# fitnessband.net
KiCad netlist of a schematic drawn in EAGLE
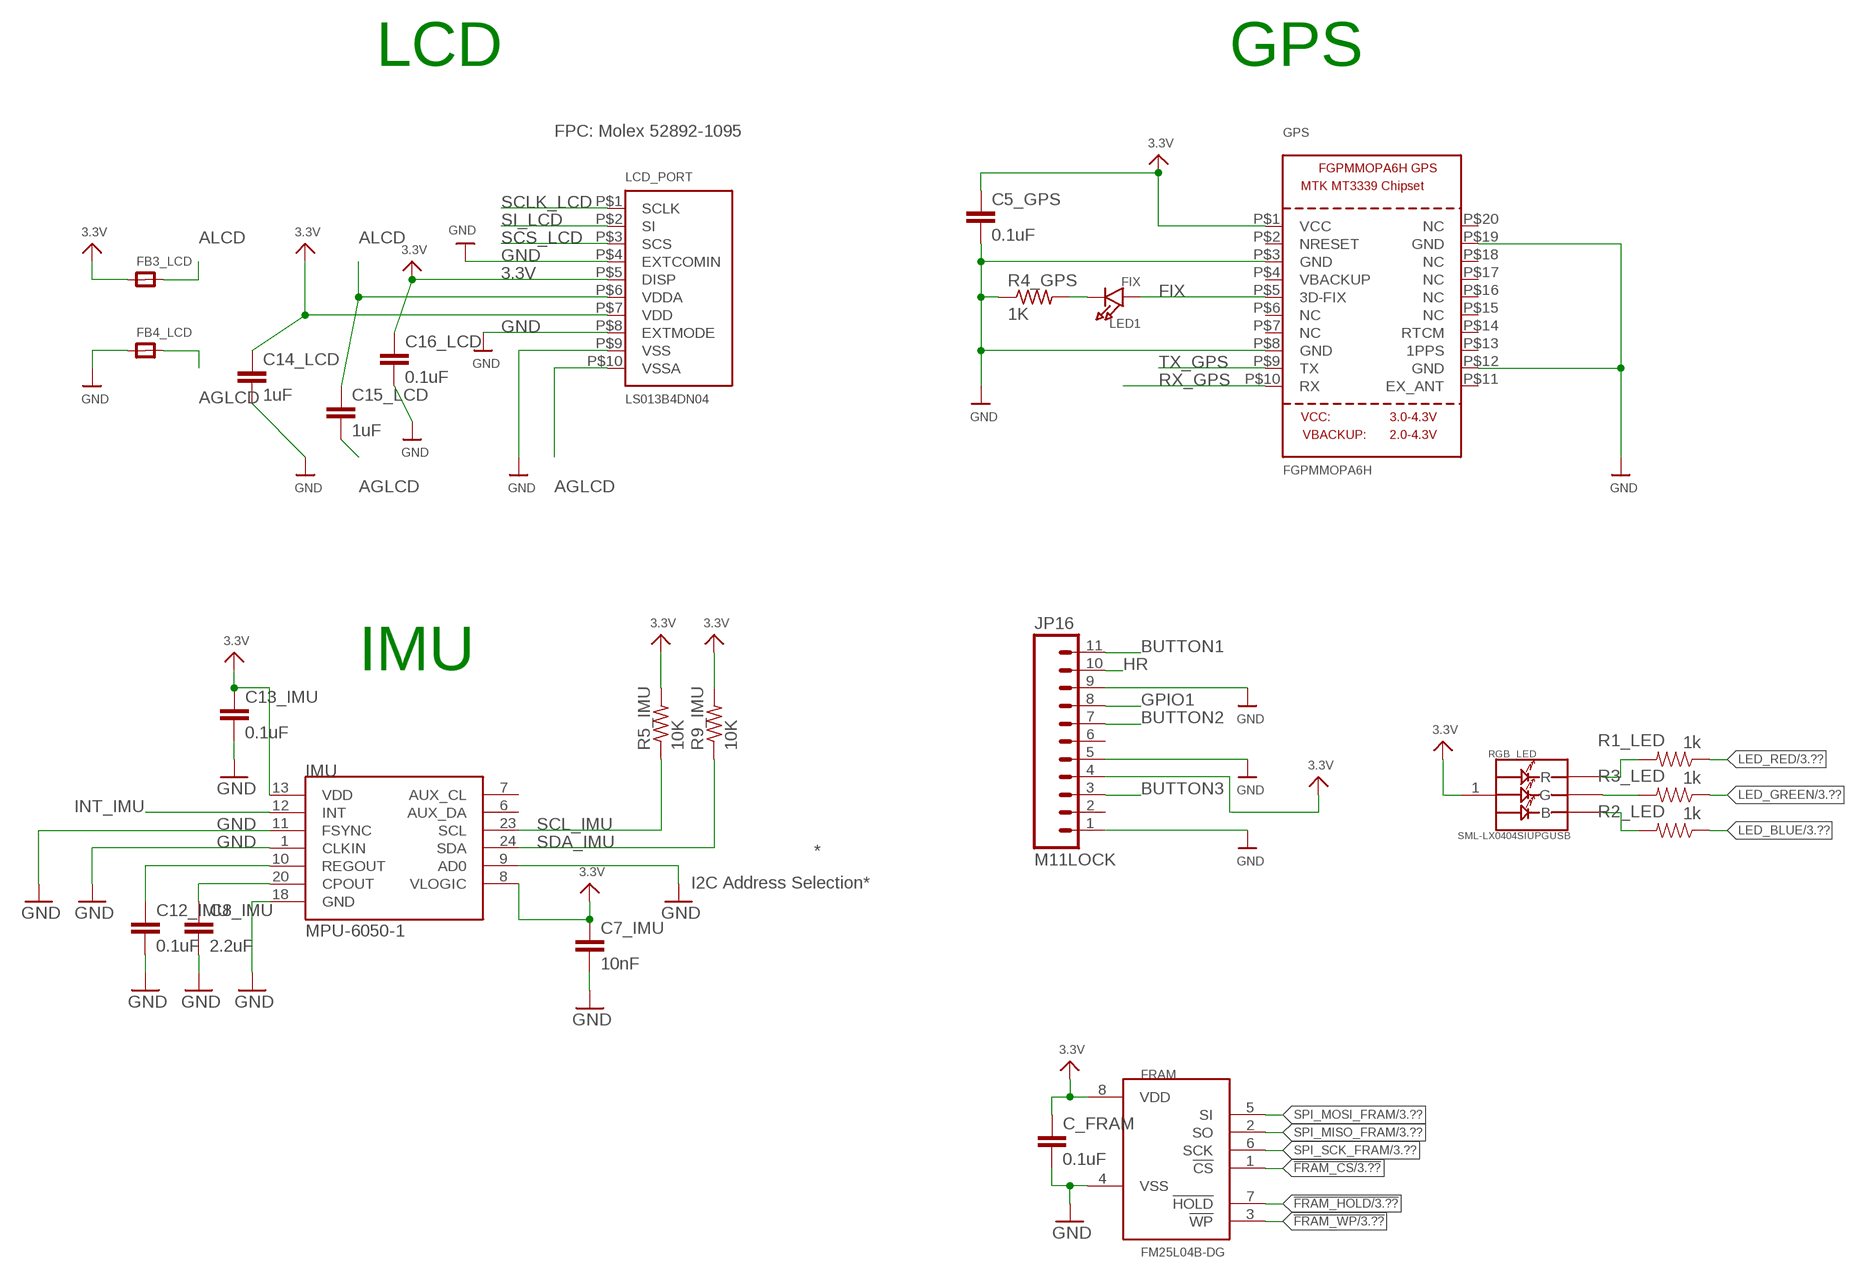
[diagram p0: schematic, sheet 1]
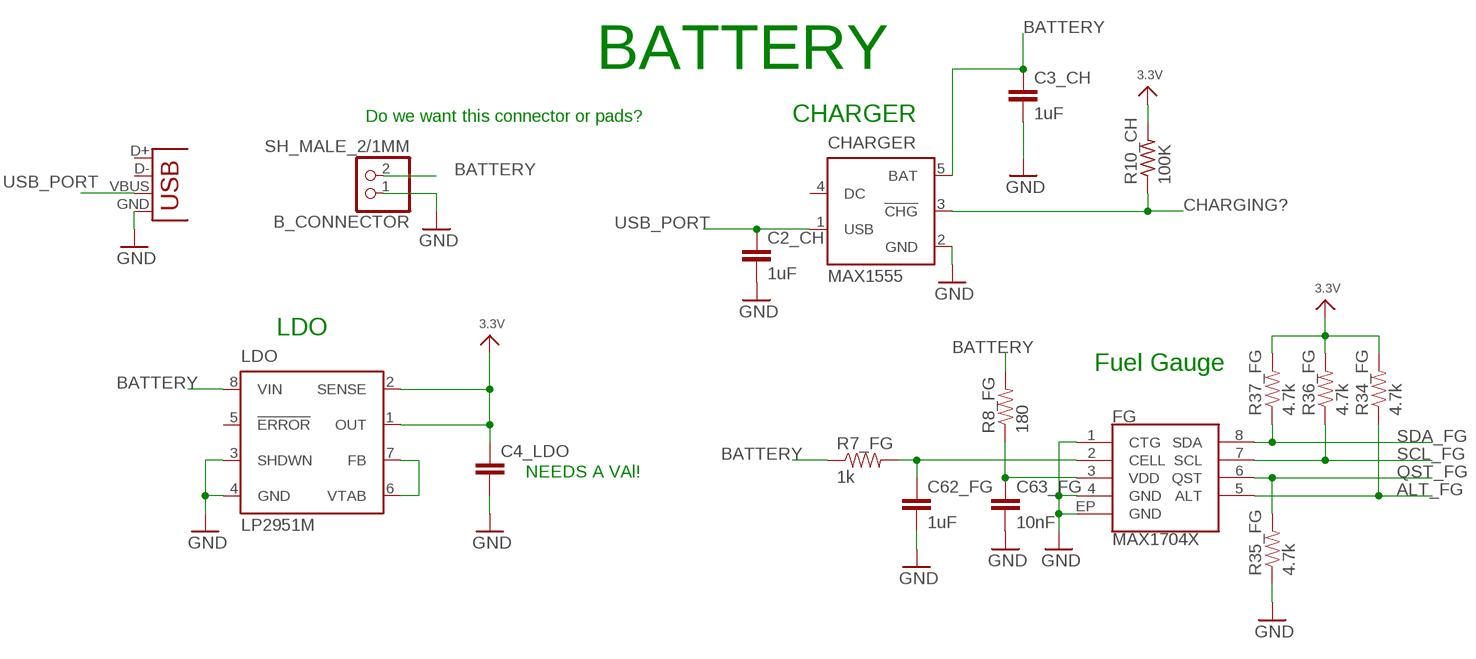
[diagram p1: schematic, sheet 2]
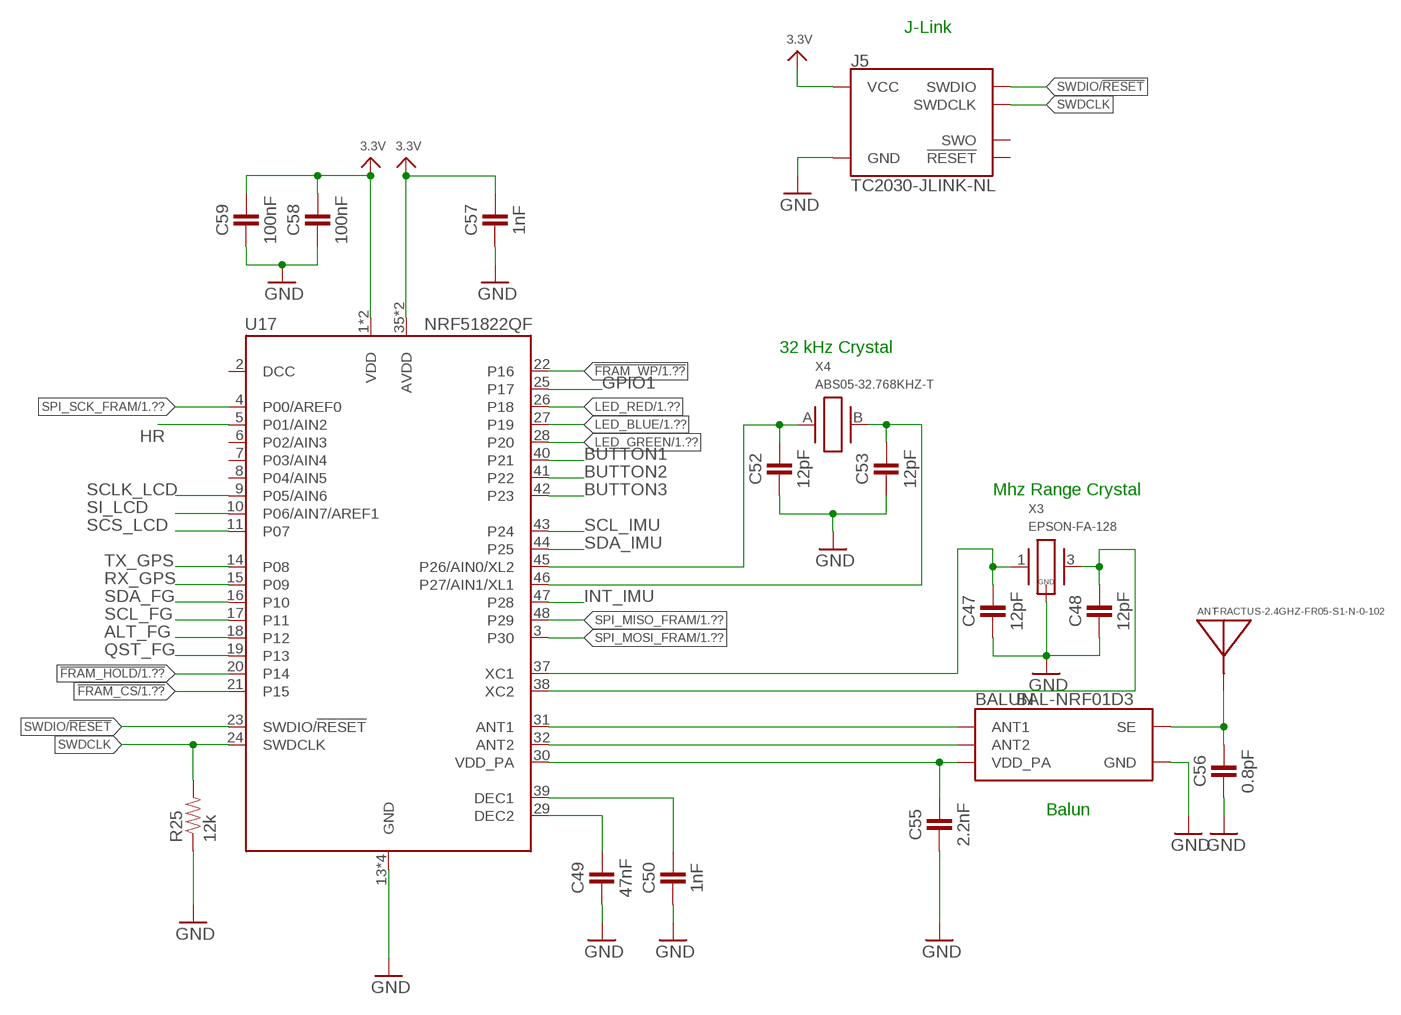
[diagram p2: schematic, sheet 3]

(export (version "E")
  (design (tool "Eeschema 10.0.6"))
  (components
    (comp (ref "C5_GPS")
      (value "0.1uF")
      (footprint "eagle-import:C0402")
      (libsource (lib "eagle-import") (part "C-EUC0402"))
    )
    (comp (ref "C7_IMU")
      (value "10nF")
      (footprint "eagle-import:C0402")
      (libsource (lib "eagle-import") (part "C-EUC0402"))
    )
    (comp (ref "C8_IMU")
      (value "2.2uF")
      (footprint "eagle-import:C0402")
      (libsource (lib "eagle-import") (part "C-EUC0402"))
    )
    (comp (ref "C12_IMU")
      (value "0.1uF")
      (footprint "eagle-import:C0402")
      (libsource (lib "eagle-import") (part "C-EUC0402"))
    )
    (comp (ref "C13_IMU")
      (value "0.1uF")
      (footprint "eagle-import:C0402")
      (libsource (lib "eagle-import") (part "C-EUC0402"))
    )
    (comp (ref "C14_LCD")
      (value "1uF")
      (footprint "eagle-import:C0402")
      (libsource (lib "eagle-import") (part "C-EUC0402"))
    )
    (comp (ref "C15_LCD")
      (value "1uF")
      (footprint "eagle-import:C0402")
      (libsource (lib "eagle-import") (part "C-EUC0402"))
    )
    (comp (ref "C16_LCD")
      (value "0.1uF")
      (footprint "eagle-import:C0402")
      (libsource (lib "eagle-import") (part "C-EUC0402"))
    )
    (comp (ref "C_FRAM")
      (value "0.1uF")
      (footprint "eagle-import:C0402")
      (libsource (lib "eagle-import") (part "C-EUC0402"))
    )
    (comp (ref "FB3_LCD")
      (value "FERRITE_0805")
      (footprint "eagle-import:_0805")
      (libsource (lib "eagle-import") (part "FERRITE_0805"))
    )
    (comp (ref "FB4_LCD")
      (value "FERRITE_0805")
      (footprint "eagle-import:_0805")
      (libsource (lib "eagle-import") (part "FERRITE_0805"))
    )
    (comp (ref "FRAM")
      (value "FM25L04B-DG")
      (footprint "eagle-import:TDFN-8")
      (libsource (lib "eagle-import") (part "FM25L04B-DG"))
    )
    (comp (ref "GPS")
      (value "FGPMMOPA6H")
      (footprint "eagle-import:FGPMMOPA6H")
      (libsource (lib "eagle-import") (part "GPS_FGPMMOPA6H"))
    )
    (comp (ref "IMU")
      (value "MPU-6050-1")
      (footprint "eagle-import:QFN-24-4MM2")
      (libsource (lib "eagle-import") (part "MPU-6050-1"))
    )
    (comp (ref "JP16")
      (value "M11LOCK")
      (footprint "eagle-import:1X11_LOCK")
      (libsource (lib "eagle-import") (part "M11LOCK"))
    )
    (comp (ref "LCD_PORT")
      (value "LS013B4DN04")
      (footprint "eagle-import:FPC_10PIN_52892-1095")
      (libsource (lib "eagle-import") (part "SHARP_MEMORYLCD_10PIN"))
    )
    (comp (ref "LED1")
      (value "FIX")
      (footprint "eagle-import:CHIPLED_0805")
      (libsource (lib "eagle-import") (part "LED0805"))
    )
    (comp (ref "R1_LED")
      (value "1k")
      (footprint "eagle-import:0402_RES")
      (libsource (lib "eagle-import") (part "RESISTOR0402_RES"))
    )
    (comp (ref "R2_LED")
      (value "1k")
      (footprint "eagle-import:0402_RES")
      (libsource (lib "eagle-import") (part "RESISTOR0402_RES"))
    )
    (comp (ref "R3_LED")
      (value "1k")
      (footprint "eagle-import:0402_RES")
      (libsource (lib "eagle-import") (part "RESISTOR0402_RES"))
    )
    (comp (ref "R4_GPS")
      (value "1K")
      (footprint "eagle-import:R0402")
      (libsource (lib "eagle-import") (part "R-US_R0402"))
    )
    (comp (ref "R5_IMU")
      (value "10K")
      (footprint "eagle-import:R0402")
      (libsource (lib "eagle-import") (part "R-US_R0402"))
    )
    (comp (ref "R9_IMU")
      (value "10K")
      (footprint "eagle-import:R0402")
      (libsource (lib "eagle-import") (part "R-US_R0402"))
    )
    (comp (ref "RGB_LED")
      (value "SML-LX0404SIUPGUSB")
      (footprint "eagle-import:1MM_SQ_4PAD")
      (libsource (lib "eagle-import") (part "SML-LX0404SIUPGUSB"))
    )
    (comp (ref "ANT")
      (value "FRACTUS-2.4GHZ-FR05-S1-N-0-102")
      (footprint "eagle-import:FRACTUS-ANTENNA-FR05-S1-N-0-102")
      (libsource (lib "eagle-import") (part "FRACTUS-2.4GHZ-FR05-S1-N-0-102"))
    )
    (comp (ref "BALUN")
      (value "BAL-NRF01D3")
      (footprint "eagle-import:BAL-NRF01D3")
      (libsource (lib "eagle-import") (part "BAL-NRF01D3"))
    )
    (comp (ref "C47")
      (value "12pF")
      (footprint "eagle-import:0402_CAP")
      (libsource (lib "eagle-import") (part "CAPACITOR"))
    )
    (comp (ref "C48")
      (value "12pF")
      (footprint "eagle-import:0402_CAP")
      (libsource (lib "eagle-import") (part "CAPACITOR"))
    )
    (comp (ref "C49")
      (value "47nF")
      (footprint "eagle-import:0402_CAP")
      (libsource (lib "eagle-import") (part "CAPACITOR"))
    )
    (comp (ref "C50")
      (value "1nF")
      (footprint "eagle-import:0402_CAP")
      (libsource (lib "eagle-import") (part "CAPACITOR"))
    )
    (comp (ref "C52")
      (value "12pF")
      (footprint "eagle-import:0402_CAP")
      (libsource (lib "eagle-import") (part "CAPACITOR"))
    )
    (comp (ref "C53")
      (value "12pF")
      (footprint "eagle-import:0402_CAP")
      (libsource (lib "eagle-import") (part "CAPACITOR"))
    )
    (comp (ref "C55")
      (value "2.2nF")
      (footprint "eagle-import:0402_CAP")
      (libsource (lib "eagle-import") (part "CAPACITOR"))
    )
    (comp (ref "C56")
      (value "0.8pF")
      (footprint "eagle-import:0402_CAP")
      (libsource (lib "eagle-import") (part "CAPACITOR"))
    )
    (comp (ref "C57")
      (value "1nF")
      (footprint "eagle-import:0402_CAP")
      (libsource (lib "eagle-import") (part "CAPACITOR"))
    )
    (comp (ref "C58")
      (value "100nF")
      (footprint "eagle-import:0402_CAP")
      (libsource (lib "eagle-import") (part "CAPACITOR"))
    )
    (comp (ref "C59")
      (value "100nF")
      (footprint "eagle-import:0402_CAP")
      (libsource (lib "eagle-import") (part "CAPACITOR"))
    )
    (comp (ref "J5")
      (value "TC2030-JLINK-NL")
      (footprint "eagle-import:TC2030-IDC-NL")
      (libsource (lib "eagle-import") (part "TC2030-JLINK-NL"))
    )
    (comp (ref "R25")
      (value "12k")
      (footprint "eagle-import:0402_RES")
      (libsource (lib "eagle-import") (part "RESISTOR0402_RES"))
    )
    (comp (ref "U17")
      (value "NRF51822QF")
      (footprint "eagle-import:QFN-48-6MM")
      (libsource (lib "eagle-import") (part "NRF51822QF"))
    )
    (comp (ref "X3")
      (value "EPSON-FA-128")
      (footprint "eagle-import:FA-128")
      (libsource (lib "eagle-import") (part "EPSON-FA-128"))
    )
    (comp (ref "X4")
      (value "ABS05-32.768KHZ-T")
      (footprint "eagle-import:ABS05")
      (libsource (lib "eagle-import") (part "ABS05-32.768KHZ-T"))
    )
    (comp (ref "B_CONNECTOR")
      (value "SH_MALE_2/1MM")
      (footprint "eagle-import:SH-1X2_1MM")
      (libsource (lib "eagle-import") (part "SH_MALE_2/1MM"))
    )
    (comp (ref "C2_CH")
      (value "1uF")
      (footprint "eagle-import:C0402")
      (libsource (lib "eagle-import") (part "C-EUC0402"))
    )
    (comp (ref "C3_CH")
      (value "1uF")
      (footprint "eagle-import:C0402")
      (libsource (lib "eagle-import") (part "C-EUC0402"))
    )
    (comp (ref "C4_LDO")
      (value "C-EUC0402")
      (footprint "eagle-import:C0402")
      (libsource (lib "eagle-import") (part "C-EUC0402"))
    )
    (comp (ref "C62_FG")
      (value "1uF")
      (footprint "eagle-import:0402-CAP")
      (libsource (lib "eagle-import") (part "CAP0402-CAP"))
    )
    (comp (ref "C63_FG")
      (value "10nF")
      (footprint "eagle-import:0402-CAP")
      (libsource (lib "eagle-import") (part "CAP0402-CAP"))
    )
    (comp (ref "CHARGER")
      (value "MAX1555")
      (footprint "eagle-import:SOT23-5L")
      (fields (field (name "MF") "MAXIM") (field (name "MPN") "MAX1555EZK+T"))
      (libsource (lib "eagle-import") (part "MAX1555"))
    )
    (comp (ref "FG")
      (value "MAX1704X")
      (footprint "eagle-import:TDFN-8")
      (libsource (lib "eagle-import") (part "MAX1704X"))
    )
    (comp (ref "LDO")
      (value "LP2951M")
      (footprint "eagle-import:SO08")
      (fields (field (name "MF") "FAIRCHILD SEMICONDUCTOR") (field (name "MPN") "LP2951CM"))
      (libsource (lib "eagle-import") (part "LP2951M"))
    )
    (comp (ref "R7_FG")
      (value "1k")
      (footprint "eagle-import:0402-RES")
      (libsource (lib "eagle-import") (part "RESISTOR0402-RES"))
    )
    (comp (ref "R8_FG")
      (value "180")
      (footprint "eagle-import:0402-RES")
      (libsource (lib "eagle-import") (part "RESISTOR0402-RES"))
    )
    (comp (ref "R10_CH")
      (value "100K")
      (footprint "eagle-import:R0402")
      (libsource (lib "eagle-import") (part "R-US_R0402"))
    )
    (comp (ref "R34_FG")
      (value "4.7k")
      (footprint "eagle-import:0402-RES")
      (libsource (lib "eagle-import") (part "RESISTOR0402-RES"))
    )
    (comp (ref "R35_FG")
      (value "4.7k")
      (footprint "eagle-import:0402-RES")
      (libsource (lib "eagle-import") (part "RESISTOR0402-RES"))
    )
    (comp (ref "R36_FG")
      (value "4.7k")
      (footprint "eagle-import:0402-RES")
      (libsource (lib "eagle-import") (part "RESISTOR0402-RES"))
    )
    (comp (ref "R37_FG")
      (value "4.7k")
      (footprint "eagle-import:0402-RES")
      (libsource (lib "eagle-import") (part "RESISTOR0402-RES"))
    )
    (comp (ref "X5")
      (value "USB-MICROB")
      (footprint "eagle-import:USB-MICROB")
      (libsource (lib "eagle-import") (part "USB-MICROB"))
    )
  )
  (nets
    (net (code "1") (name "3.3V") (class "Default")
      (node (ref "C13_IMU") (pin "1") (pinfunction "1_1") (pintype "passive"))
      (node (ref "C14_LCD") (pin "1") (pinfunction "1_1") (pintype "passive"))
      (node (ref "C16_LCD") (pin "1") (pinfunction "1_1") (pintype "passive"))
      (node (ref "C4_LDO") (pin "1") (pinfunction "1_1") (pintype "passive"))
      (node (ref "C57") (pin "1") (pinfunction "1_1") (pintype "bidirectional"))
      (node (ref "C58") (pin "1") (pinfunction "1_1") (pintype "bidirectional"))
      (node (ref "C59") (pin "1") (pinfunction "1_1") (pintype "bidirectional"))
      (node (ref "C5_GPS") (pin "1") (pinfunction "1_1") (pintype "passive"))
      (node (ref "C7_IMU") (pin "1") (pinfunction "1_1") (pintype "passive"))
      (node (ref "C_FRAM") (pin "1") (pinfunction "1_1") (pintype "passive"))
      (node (ref "FB3_LCD") (pin "1") (pinfunction "P$1_1") (pintype "passive"))
      (node (ref "FRAM") (pin "8") (pinfunction "VDD_8") (pintype "bidirectional"))
      (node (ref "GPS") (pin "P$1") (pinfunction "VCC_P$1") (pintype "bidirectional"))
      (node (ref "IMU") (pin "13") (pinfunction "VDD_13") (pintype "bidirectional"))
      (node (ref "IMU") (pin "8") (pinfunction "VLOGIC_8") (pintype "bidirectional"))
      (node (ref "J5") (pin "1") (pinfunction "VCC_1") (pintype "bidirectional"))
      (node (ref "JP16") (pin "4") (pinfunction "4_4") (pintype "passive"))
      (node (ref "LCD_PORT") (pin "P$5") (pinfunction "DISP_P$5") (pintype "input"))
      (node (ref "LCD_PORT") (pin "P$7") (pinfunction "VDD_P$7") (pintype "power_in"))
      (node (ref "LDO") (pin "1") (pinfunction "OUT_1") (pintype "output"))
      (node (ref "LDO") (pin "2") (pinfunction "SENSE_2") (pintype "input"))
      (node (ref "R10_CH") (pin "2") (pinfunction "2_2") (pintype "passive"))
      (node (ref "R34_FG") (pin "2") (pinfunction "2_2") (pintype "passive"))
      (node (ref "R36_FG") (pin "2") (pinfunction "2_2") (pintype "passive"))
      (node (ref "R37_FG") (pin "2") (pinfunction "2_2") (pintype "passive"))
      (node (ref "R5_IMU") (pin "2") (pinfunction "2_2") (pintype "passive"))
      (node (ref "R9_IMU") (pin "2") (pinfunction "2_2") (pintype "passive"))
      (node (ref "RGB_LED") (pin "1") (pinfunction "VDD_1") (pintype "bidirectional"))
      (node (ref "U17") (pin "1") (pinfunction "VDD_1") (pintype "bidirectional"))
      (node (ref "U17") (pin "12") (pinfunction "VDD_12") (pintype "bidirectional"))
      (node (ref "U17") (pin "35") (pinfunction "AVDD_35") (pintype "bidirectional"))
      (node (ref "U17") (pin "36") (pinfunction "AVDD_36") (pintype "bidirectional"))
    )
    (net (code "2") (name "AGLCD") (class "Default")
      (node (ref "C15_LCD") (pin "2") (pinfunction "2_2") (pintype "passive"))
      (node (ref "FB4_LCD") (pin "2") (pinfunction "P$2_2") (pintype "passive"))
      (node (ref "LCD_PORT") (pin "P$10") (pinfunction "VSSA_P$10") (pintype "power_in"))
    )
    (net (code "3") (name "ALCD") (class "Default")
      (node (ref "C15_LCD") (pin "1") (pinfunction "1_1") (pintype "passive"))
      (node (ref "FB3_LCD") (pin "2") (pinfunction "P$2_2") (pintype "passive"))
      (node (ref "LCD_PORT") (pin "P$6") (pinfunction "VDDA_P$6") (pintype "power_in"))
    )
    (net (code "4") (name "ALT_FG") (class "Default")
      (node (ref "FG") (pin "5") (pinfunction "ALT_5") (pintype "bidirectional"))
      (node (ref "R34_FG") (pin "1") (pinfunction "1_1") (pintype "passive"))
      (node (ref "U17") (pin "18") (pinfunction "P12_18") (pintype "bidirectional"))
    )
    (net (code "5") (name "BATTERY") (class "Default")
      (node (ref "B_CONNECTOR") (pin "2") (pinfunction "2_2") (pintype "passive"))
      (node (ref "C3_CH") (pin "1") (pinfunction "1_1") (pintype "passive"))
      (node (ref "CHARGER") (pin "5") (pinfunction "BAT_5") (pintype "passive"))
      (node (ref "LDO") (pin "8") (pinfunction "VIN_8") (pintype "input"))
      (node (ref "R7_FG") (pin "1") (pinfunction "1_1") (pintype "passive"))
      (node (ref "R8_FG") (pin "2") (pinfunction "2_2") (pintype "passive"))
    )
    (net (code "6") (name "BUTTON1") (class "Default")
      (node (ref "JP16") (pin "11") (pinfunction "11_11") (pintype "passive"))
      (node (ref "U17") (pin "40") (pinfunction "P21_40") (pintype "bidirectional"))
    )
    (net (code "7") (name "BUTTON2") (class "Default")
      (node (ref "JP16") (pin "7") (pinfunction "7_7") (pintype "passive"))
      (node (ref "U17") (pin "41") (pinfunction "P22_41") (pintype "bidirectional"))
    )
    (net (code "8") (name "BUTTON3") (class "Default")
      (node (ref "JP16") (pin "3") (pinfunction "3_3") (pintype "passive"))
      (node (ref "U17") (pin "42") (pinfunction "P23_42") (pintype "bidirectional"))
    )
    (net (code "9") (name "CHARGING?") (class "Default")
      (node (ref "CHARGER") (pin "3") (pinfunction "~{CHG}_3") (pintype "output"))
      (node (ref "R10_CH") (pin "1") (pinfunction "1_1") (pintype "passive"))
    )
    (net (code "10") (name "FIX") (class "Default")
      (node (ref "GPS") (pin "P$5") (pinfunction "3D-FIX_P$5") (pintype "bidirectional"))
      (node (ref "LED1") (pin "A") (pinfunction "A_A") (pintype "passive"))
    )
    (net (code "11") (name "GND") (class "Default")
      (node (ref "BALUN") (pin "GND") (pinfunction "GND_GND") (pintype "bidirectional"))
      (node (ref "B_CONNECTOR") (pin "1") (pinfunction "1_1") (pintype "passive"))
      (node (ref "C12_IMU") (pin "2") (pinfunction "2_2") (pintype "passive"))
      (node (ref "C13_IMU") (pin "2") (pinfunction "2_2") (pintype "passive"))
      (node (ref "C14_LCD") (pin "2") (pinfunction "2_2") (pintype "passive"))
      (node (ref "C16_LCD") (pin "2") (pinfunction "2_2") (pintype "passive"))
      (node (ref "C2_CH") (pin "2") (pinfunction "2_2") (pintype "passive"))
      (node (ref "C3_CH") (pin "2") (pinfunction "2_2") (pintype "passive"))
      (node (ref "C47") (pin "2") (pinfunction "2_2") (pintype "bidirectional"))
      (node (ref "C48") (pin "2") (pinfunction "2_2") (pintype "bidirectional"))
      (node (ref "C49") (pin "2") (pinfunction "2_2") (pintype "bidirectional"))
      (node (ref "C4_LDO") (pin "2") (pinfunction "2_2") (pintype "passive"))
      (node (ref "C50") (pin "2") (pinfunction "2_2") (pintype "bidirectional"))
      (node (ref "C52") (pin "2") (pinfunction "2_2") (pintype "bidirectional"))
      (node (ref "C53") (pin "2") (pinfunction "2_2") (pintype "bidirectional"))
      (node (ref "C55") (pin "2") (pinfunction "2_2") (pintype "bidirectional"))
      (node (ref "C56") (pin "2") (pinfunction "2_2") (pintype "bidirectional"))
      (node (ref "C57") (pin "2") (pinfunction "2_2") (pintype "bidirectional"))
      (node (ref "C58") (pin "2") (pinfunction "2_2") (pintype "bidirectional"))
      (node (ref "C59") (pin "2") (pinfunction "2_2") (pintype "bidirectional"))
      (node (ref "C5_GPS") (pin "2") (pinfunction "2_2") (pintype "passive"))
      (node (ref "C62_FG") (pin "2") (pinfunction "2_2") (pintype "passive"))
      (node (ref "C63_FG") (pin "2") (pinfunction "2_2") (pintype "passive"))
      (node (ref "C7_IMU") (pin "2") (pinfunction "2_2") (pintype "passive"))
      (node (ref "C8_IMU") (pin "2") (pinfunction "2_2") (pintype "passive"))
      (node (ref "CHARGER") (pin "2") (pinfunction "GND_2") (pintype "power_in"))
      (node (ref "C_FRAM") (pin "2") (pinfunction "2_2") (pintype "passive"))
      (node (ref "FB4_LCD") (pin "1") (pinfunction "P$1_1") (pintype "passive"))
      (node (ref "FG") (pin "1") (pinfunction "CTG_1") (pintype "bidirectional"))
      (node (ref "FG") (pin "4") (pinfunction "GND_4") (pintype "bidirectional"))
      (node (ref "FG") (pin "EP") (pinfunction "GND_EP") (pintype "bidirectional"))
      (node (ref "FRAM") (pin "4") (pinfunction "VSS_4") (pintype "bidirectional"))
      (node (ref "GPS") (pin "P$12") (pinfunction "GND_P$12") (pintype "bidirectional"))
      (node (ref "GPS") (pin "P$19") (pinfunction "GND_P$19") (pintype "bidirectional"))
      (node (ref "GPS") (pin "P$3") (pinfunction "GND_P$3") (pintype "bidirectional"))
      (node (ref "GPS") (pin "P$8") (pinfunction "GND_P$8") (pintype "bidirectional"))
      (node (ref "IMU") (pin "1") (pinfunction "CLKIN_1") (pintype "bidirectional"))
      (node (ref "IMU") (pin "11") (pinfunction "FSYNC_11") (pintype "bidirectional"))
      (node (ref "IMU") (pin "18") (pinfunction "GND_18") (pintype "bidirectional"))
      (node (ref "IMU") (pin "9") (pinfunction "AD0_9") (pintype "bidirectional"))
      (node (ref "J5") (pin "5") (pinfunction "GND_5") (pintype "bidirectional"))
      (node (ref "JP16") (pin "1") (pinfunction "1_1") (pintype "passive"))
      (node (ref "JP16") (pin "5") (pinfunction "5_5") (pintype "passive"))
      (node (ref "JP16") (pin "9") (pinfunction "9_9") (pintype "passive"))
      (node (ref "LCD_PORT") (pin "P$4") (pinfunction "EXTCOMIN_P$4") (pintype "input"))
      (node (ref "LCD_PORT") (pin "P$8") (pinfunction "EXTMODE_P$8") (pintype "input"))
      (node (ref "LCD_PORT") (pin "P$9") (pinfunction "VSS_P$9") (pintype "power_in"))
      (node (ref "LDO") (pin "3") (pinfunction "SHDWN_3") (pintype "input"))
      (node (ref "LDO") (pin "4") (pinfunction "GND_4") (pintype "power_in"))
      (node (ref "R25") (pin "1") (pinfunction "1_1") (pintype "passive"))
      (node (ref "R35_FG") (pin "1") (pinfunction "1_1") (pintype "passive"))
      (node (ref "R4_GPS") (pin "1") (pinfunction "1_1") (pintype "passive"))
      (node (ref "U17") (pin "13") (pinfunction "GND_13") (pintype "bidirectional"))
      (node (ref "U17") (pin "33") (pinfunction "GND_33") (pintype "bidirectional"))
      (node (ref "U17") (pin "34") (pinfunction "GND_34") (pintype "bidirectional"))
      (node (ref "U17") (pin "GND") (pinfunction "GND_GND") (pintype "bidirectional"))
      (node (ref "X3") (pin "2") (pinfunction "GND_2") (pintype "bidirectional"))
      (node (ref "X3") (pin "4") (pinfunction "GND_4") (pintype "bidirectional"))
      (node (ref "X5") (pin "GND") (pinfunction "GND_GND") (pintype "bidirectional"))
    )
    (net (code "12") (name "GPIO1") (class "Default")
      (node (ref "JP16") (pin "8") (pinfunction "8_8") (pintype "passive"))
      (node (ref "U17") (pin "25") (pinfunction "P17_25") (pintype "bidirectional"))
    )
    (net (code "13") (name "HR") (class "Default")
      (node (ref "JP16") (pin "10") (pinfunction "10_10") (pintype "passive"))
      (node (ref "U17") (pin "5") (pinfunction "P01/AIN2_5") (pintype "bidirectional"))
    )
    (net (code "14") (name "INT_IMU") (class "Default")
      (node (ref "IMU") (pin "12") (pinfunction "INT_12") (pintype "bidirectional"))
      (node (ref "U17") (pin "47") (pinfunction "P28_47") (pintype "bidirectional"))
    )
    (net (code "15") (name "LED_BLUE") (class "Default")
      (node (ref "R2_LED") (pin "1") (pinfunction "1_1") (pintype "passive"))
      (node (ref "U17") (pin "27") (pinfunction "P19_27") (pintype "bidirectional"))
    )
    (net (code "16") (name "LED_GREEN") (class "Default")
      (node (ref "R3_LED") (pin "1") (pinfunction "1_1") (pintype "passive"))
      (node (ref "U17") (pin "28") (pinfunction "P20_28") (pintype "bidirectional"))
    )
    (net (code "17") (name "LED_RED") (class "Default")
      (node (ref "R1_LED") (pin "1") (pinfunction "1_1") (pintype "passive"))
      (node (ref "U17") (pin "26") (pinfunction "P18_26") (pintype "bidirectional"))
    )
    (net (code "18") (name "Net-(ANT-ANTENNA)") (class "Default")
      (node (ref "ANT") (pin "1") (pinfunction "ANTENNA_1") (pintype "bidirectional"))
      (node (ref "BALUN") (pin "SE") (pinfunction "SE_SE") (pintype "bidirectional"))
      (node (ref "C56") (pin "1") (pinfunction "1_1") (pintype "bidirectional"))
    )
    (net (code "19") (name "Net-(BALUN-VDD_PA)") (class "Default")
      (node (ref "BALUN") (pin "VCC") (pinfunction "VDD_PA_VCC") (pintype "bidirectional"))
      (node (ref "C55") (pin "1") (pinfunction "1_1") (pintype "bidirectional"))
      (node (ref "U17") (pin "30") (pinfunction "VDD_PA_30") (pintype "bidirectional"))
    )
    (net (code "20") (name "Net-(FG-CELL)") (class "Default")
      (node (ref "C62_FG") (pin "1") (pinfunction "1_1") (pintype "passive"))
      (node (ref "FG") (pin "2") (pinfunction "CELL_2") (pintype "bidirectional"))
      (node (ref "R7_FG") (pin "2") (pinfunction "2_2") (pintype "passive"))
    )
    (net (code "21") (name "Net-(FG-VDD)") (class "Default")
      (node (ref "C63_FG") (pin "1") (pinfunction "1_1") (pintype "passive"))
      (node (ref "FG") (pin "3") (pinfunction "VDD_3") (pintype "bidirectional"))
      (node (ref "R8_FG") (pin "1") (pinfunction "1_1") (pintype "passive"))
    )
    (net (code "22") (name "Net-(IMU-CPOUT)") (class "Default")
      (node (ref "C8_IMU") (pin "1") (pinfunction "1_1") (pintype "passive"))
      (node (ref "IMU") (pin "20") (pinfunction "CPOUT_20") (pintype "bidirectional"))
    )
    (net (code "23") (name "Net-(IMU-REGOUT)") (class "Default")
      (node (ref "C12_IMU") (pin "1") (pinfunction "1_1") (pintype "passive"))
      (node (ref "IMU") (pin "10") (pinfunction "REGOUT_10") (pintype "bidirectional"))
    )
    (net (code "24") (name "Net-(LDO-FB)") (class "Default")
      (node (ref "LDO") (pin "6") (pinfunction "VTAB_6") (pintype "input"))
      (node (ref "LDO") (pin "7") (pinfunction "FB_7") (pintype "input"))
    )
    (net (code "25") (name "Net-(LED1-PadC)") (class "Default")
      (node (ref "LED1") (pin "C") (pinfunction "C_C") (pintype "passive"))
      (node (ref "R4_GPS") (pin "2") (pinfunction "2_2") (pintype "passive"))
    )
    (net (code "26") (name "Net-(RGB_LED-B)") (class "Default")
      (node (ref "R2_LED") (pin "2") (pinfunction "2_2") (pintype "passive"))
      (node (ref "RGB_LED") (pin "3") (pinfunction "B_3") (pintype "output"))
    )
    (net (code "27") (name "Net-(RGB_LED-G)") (class "Default")
      (node (ref "R3_LED") (pin "2") (pinfunction "2_2") (pintype "passive"))
      (node (ref "RGB_LED") (pin "4") (pinfunction "G_4") (pintype "output"))
    )
    (net (code "28") (name "Net-(RGB_LED-R)") (class "Default")
      (node (ref "R1_LED") (pin "2") (pinfunction "2_2") (pintype "passive"))
      (node (ref "RGB_LED") (pin "2") (pinfunction "R_2") (pintype "output"))
    )
    (net (code "29") (name "Net-(U17-ANT1)") (class "Default")
      (node (ref "BALUN") (pin "ANT1") (pinfunction "ANT1_ANT1") (pintype "bidirectional"))
      (node (ref "U17") (pin "31") (pinfunction "ANT1_31") (pintype "bidirectional"))
    )
    (net (code "30") (name "Net-(U17-ANT2)") (class "Default")
      (node (ref "BALUN") (pin "ANT2") (pinfunction "ANT2_ANT2") (pintype "bidirectional"))
      (node (ref "U17") (pin "32") (pinfunction "ANT2_32") (pintype "bidirectional"))
    )
    (net (code "31") (name "Net-(U17-DEC1)") (class "Default")
      (node (ref "C50") (pin "1") (pinfunction "1_1") (pintype "bidirectional"))
      (node (ref "U17") (pin "39") (pinfunction "DEC1_39") (pintype "bidirectional"))
    )
    (net (code "32") (name "Net-(U17-DEC2)") (class "Default")
      (node (ref "C49") (pin "1") (pinfunction "1_1") (pintype "bidirectional"))
      (node (ref "U17") (pin "29") (pinfunction "DEC2_29") (pintype "bidirectional"))
    )
    (net (code "33") (name "Net-(U17-P26{slash}AIN0{slash}XL2)") (class "Default")
      (node (ref "C52") (pin "1") (pinfunction "1_1") (pintype "bidirectional"))
      (node (ref "U17") (pin "45") (pinfunction "P26/AIN0/XL2_45") (pintype "bidirectional"))
      (node (ref "X4") (pin "A") (pinfunction "1_A") (pintype "bidirectional"))
    )
    (net (code "34") (name "Net-(U17-P27{slash}AIN1{slash}XL1)") (class "Default")
      (node (ref "C53") (pin "1") (pinfunction "1_1") (pintype "bidirectional"))
      (node (ref "U17") (pin "46") (pinfunction "P27/AIN1/XL1_46") (pintype "bidirectional"))
      (node (ref "X4") (pin "B") (pinfunction "2_B") (pintype "bidirectional"))
    )
    (net (code "35") (name "Net-(U17-XC1)") (class "Default")
      (node (ref "C47") (pin "1") (pinfunction "1_1") (pintype "bidirectional"))
      (node (ref "U17") (pin "37") (pinfunction "XC1_37") (pintype "bidirectional"))
      (node (ref "X3") (pin "1") (pinfunction "1_1") (pintype "bidirectional"))
    )
    (net (code "36") (name "Net-(U17-XC2)") (class "Default")
      (node (ref "C48") (pin "1") (pinfunction "1_1") (pintype "bidirectional"))
      (node (ref "U17") (pin "38") (pinfunction "XC2_38") (pintype "bidirectional"))
      (node (ref "X3") (pin "3") (pinfunction "2_3") (pintype "bidirectional"))
    )
    (net (code "37") (name "QST_FG") (class "Default")
      (node (ref "FG") (pin "6") (pinfunction "QST_6") (pintype "bidirectional"))
      (node (ref "R35_FG") (pin "2") (pinfunction "2_2") (pintype "passive"))
      (node (ref "U17") (pin "19") (pinfunction "P13_19") (pintype "bidirectional"))
    )
    (net (code "38") (name "RX_GPS") (class "Default")
      (node (ref "GPS") (pin "P$10") (pinfunction "RX_P$10") (pintype "bidirectional"))
      (node (ref "U17") (pin "15") (pinfunction "P09_15") (pintype "bidirectional"))
    )
    (net (code "39") (name "SCLK_LCD") (class "Default")
      (node (ref "LCD_PORT") (pin "P$1") (pinfunction "SCLK_P$1") (pintype "input"))
      (node (ref "U17") (pin "9") (pinfunction "P05/AIN6_9") (pintype "bidirectional"))
    )
    (net (code "40") (name "SCL_FG") (class "Default")
      (node (ref "FG") (pin "7") (pinfunction "SCL_7") (pintype "bidirectional"))
      (node (ref "R36_FG") (pin "1") (pinfunction "1_1") (pintype "passive"))
      (node (ref "U17") (pin "17") (pinfunction "P11_17") (pintype "bidirectional"))
    )
    (net (code "41") (name "SCL_IMU") (class "Default")
      (node (ref "IMU") (pin "23") (pinfunction "SCL_23") (pintype "bidirectional"))
      (node (ref "R5_IMU") (pin "1") (pinfunction "1_1") (pintype "passive"))
      (node (ref "U17") (pin "43") (pinfunction "P24_43") (pintype "bidirectional"))
    )
    (net (code "42") (name "SCS_LCD") (class "Default")
      (node (ref "LCD_PORT") (pin "P$3") (pinfunction "SCS_P$3") (pintype "input"))
      (node (ref "U17") (pin "11") (pinfunction "P07_11") (pintype "bidirectional"))
    )
    (net (code "43") (name "SDA_FG") (class "Default")
      (node (ref "FG") (pin "8") (pinfunction "SDA_8") (pintype "bidirectional"))
      (node (ref "R37_FG") (pin "1") (pinfunction "1_1") (pintype "passive"))
      (node (ref "U17") (pin "16") (pinfunction "P10_16") (pintype "bidirectional"))
    )
    (net (code "44") (name "SDA_IMU") (class "Default")
      (node (ref "IMU") (pin "24") (pinfunction "SDA_24") (pintype "bidirectional"))
      (node (ref "R9_IMU") (pin "1") (pinfunction "1_1") (pintype "passive"))
      (node (ref "U17") (pin "44") (pinfunction "P25_44") (pintype "bidirectional"))
    )
    (net (code "45") (name "SI_LCD") (class "Default")
      (node (ref "LCD_PORT") (pin "P$2") (pinfunction "SI_P$2") (pintype "input"))
      (node (ref "U17") (pin "10") (pinfunction "P06/AIN7/AREF1_10") (pintype "bidirectional"))
    )
    (net (code "46") (name "SPI_MISO_FRAM") (class "Default")
      (node (ref "FRAM") (pin "2") (pinfunction "SO_2") (pintype "bidirectional"))
      (node (ref "U17") (pin "48") (pinfunction "P29_48") (pintype "bidirectional"))
    )
    (net (code "47") (name "SPI_MOSI_FRAM") (class "Default")
      (node (ref "FRAM") (pin "5") (pinfunction "SI_5") (pintype "bidirectional"))
      (node (ref "U17") (pin "3") (pinfunction "P30_3") (pintype "bidirectional"))
    )
    (net (code "48") (name "SPI_SCK_FRAM") (class "Default")
      (node (ref "FRAM") (pin "6") (pinfunction "SCK_6") (pintype "bidirectional"))
      (node (ref "U17") (pin "4") (pinfunction "P00/AREF0_4") (pintype "bidirectional"))
    )
    (net (code "49") (name "SWDCLK") (class "Default")
      (node (ref "J5") (pin "4") (pinfunction "SWDCLK_4") (pintype "bidirectional"))
      (node (ref "R25") (pin "2") (pinfunction "2_2") (pintype "passive"))
      (node (ref "U17") (pin "24") (pinfunction "SWDCLK_24") (pintype "bidirectional"))
    )
    (net (code "50") (name "SWDIO{slash}~{RESET}") (class "Default")
      (node (ref "J5") (pin "2") (pinfunction "SWDIO_2") (pintype "bidirectional"))
      (node (ref "U17") (pin "23") (pinfunction "SWDIO/~{RESET}_23") (pintype "bidirectional"))
    )
    (net (code "51") (name "TX_GPS") (class "Default")
      (node (ref "GPS") (pin "P$9") (pinfunction "TX_P$9") (pintype "bidirectional"))
      (node (ref "U17") (pin "14") (pinfunction "P08_14") (pintype "bidirectional"))
    )
    (net (code "52") (name "USB_PORT") (class "Default")
      (node (ref "C2_CH") (pin "1") (pinfunction "1_1") (pintype "passive"))
      (node (ref "CHARGER") (pin "1") (pinfunction "USB_1") (pintype "input"))
      (node (ref "X5") (pin "VBUS") (pinfunction "VBUS_VBUS") (pintype "bidirectional"))
    )
    (net (code "53") (name "unconnected-(CHARGER-DC-Pad4)") (class "Default")
      (node (ref "CHARGER") (pin "4") (pinfunction "DC_4") (pintype "input"))
    )
    (net (code "54") (name "unconnected-(GPS-1PPS-PadP$13)") (class "Default")
      (node (ref "GPS") (pin "P$13") (pinfunction "1PPS_P$13") (pintype "bidirectional"))
    )
    (net (code "55") (name "unconnected-(GPS-EX_ANT-PadP$11)") (class "Default")
      (node (ref "GPS") (pin "P$11") (pinfunction "EX_ANT_P$11") (pintype "bidirectional"))
    )
    (net (code "56") (name "unconnected-(GPS-NC-PadP$6)") (class "Default")
      (node (ref "GPS") (pin "P$6") (pinfunction "NC_P$6") (pintype "bidirectional"))
    )
    (net (code "57") (name "unconnected-(GPS-NC-PadP$7)") (class "Default")
      (node (ref "GPS") (pin "P$7") (pinfunction "NC_P$7") (pintype "bidirectional"))
    )
    (net (code "58") (name "unconnected-(GPS-NC-PadP$15)") (class "Default")
      (node (ref "GPS") (pin "P$15") (pinfunction "NC_P$15") (pintype "bidirectional"))
    )
    (net (code "59") (name "unconnected-(GPS-NC-PadP$16)") (class "Default")
      (node (ref "GPS") (pin "P$16") (pinfunction "NC_P$16") (pintype "bidirectional"))
    )
    (net (code "60") (name "unconnected-(GPS-NC-PadP$17)") (class "Default")
      (node (ref "GPS") (pin "P$17") (pinfunction "NC_P$17") (pintype "bidirectional"))
    )
    (net (code "61") (name "unconnected-(GPS-NC-PadP$18)") (class "Default")
      (node (ref "GPS") (pin "P$18") (pinfunction "NC_P$18") (pintype "bidirectional"))
    )
    (net (code "62") (name "unconnected-(GPS-NC-PadP$20)") (class "Default")
      (node (ref "GPS") (pin "P$20") (pinfunction "NC_P$20") (pintype "bidirectional"))
    )
    (net (code "63") (name "unconnected-(GPS-NRESET-PadP$2)") (class "Default")
      (node (ref "GPS") (pin "P$2") (pinfunction "NRESET_P$2") (pintype "bidirectional"))
    )
    (net (code "64") (name "unconnected-(GPS-RTCM-PadP$14)") (class "Default")
      (node (ref "GPS") (pin "P$14") (pinfunction "RTCM_P$14") (pintype "bidirectional"))
    )
    (net (code "65") (name "unconnected-(GPS-VBACKUP-PadP$4)") (class "Default")
      (node (ref "GPS") (pin "P$4") (pinfunction "VBACKUP_P$4") (pintype "bidirectional"))
    )
    (net (code "66") (name "unconnected-(IMU-AUX_CL-Pad7)") (class "Default")
      (node (ref "IMU") (pin "7") (pinfunction "AUX_CL_7") (pintype "bidirectional"))
    )
    (net (code "67") (name "unconnected-(IMU-AUX_DA-Pad6)") (class "Default")
      (node (ref "IMU") (pin "6") (pinfunction "AUX_DA_6") (pintype "bidirectional"))
    )
    (net (code "68") (name "unconnected-(J5-SWO-Pad6)") (class "Default")
      (node (ref "J5") (pin "6") (pinfunction "SWO_6") (pintype "bidirectional"))
    )
    (net (code "69") (name "unconnected-(J5-~{RESET}-Pad3)") (class "Default")
      (node (ref "J5") (pin "3") (pinfunction "~{RESET}_3") (pintype "bidirectional"))
    )
    (net (code "70") (name "unconnected-(JP16-Pad2)") (class "Default")
      (node (ref "JP16") (pin "2") (pinfunction "2_2") (pintype "passive"))
    )
    (net (code "71") (name "unconnected-(JP16-Pad6)") (class "Default")
      (node (ref "JP16") (pin "6") (pinfunction "6_6") (pintype "passive"))
    )
    (net (code "72") (name "unconnected-(LDO-~{ERROR}-Pad5)") (class "Default")
      (node (ref "LDO") (pin "5") (pinfunction "~{ERROR}_5") (pintype "output"))
    )
    (net (code "73") (name "unconnected-(U17-DCC-Pad2)") (class "Default")
      (node (ref "U17") (pin "2") (pinfunction "DCC_2") (pintype "bidirectional"))
    )
    (net (code "74") (name "unconnected-(U17-P02{slash}AIN3-Pad6)") (class "Default")
      (node (ref "U17") (pin "6") (pinfunction "P02/AIN3_6") (pintype "bidirectional"))
    )
    (net (code "75") (name "unconnected-(U17-P03{slash}AIN4-Pad7)") (class "Default")
      (node (ref "U17") (pin "7") (pinfunction "P03/AIN4_7") (pintype "bidirectional"))
    )
    (net (code "76") (name "unconnected-(U17-P04{slash}AIN5-Pad8)") (class "Default")
      (node (ref "U17") (pin "8") (pinfunction "P04/AIN5_8") (pintype "bidirectional"))
    )
    (net (code "77") (name "unconnected-(X5-PadD+)") (class "Default")
      (node (ref "X5") (pin "D+") (pinfunction "D+_D+") (pintype "bidirectional"))
    )
    (net (code "78") (name "unconnected-(X5-PadD-)") (class "Default")
      (node (ref "X5") (pin "D-") (pinfunction "D-_D-") (pintype "bidirectional"))
    )
    (net (code "79") (name "~{FRAM_CS}") (class "Default")
      (node (ref "FRAM") (pin "1") (pinfunction "~{CS}_1") (pintype "bidirectional"))
      (node (ref "U17") (pin "21") (pinfunction "P15_21") (pintype "bidirectional"))
    )
    (net (code "80") (name "~{FRAM_HOLD}") (class "Default")
      (node (ref "FRAM") (pin "7") (pinfunction "~{HOLD}_7") (pintype "bidirectional"))
      (node (ref "U17") (pin "20") (pinfunction "P14_20") (pintype "bidirectional"))
    )
    (net (code "81") (name "~{FRAM_WP}") (class "Default")
      (node (ref "FRAM") (pin "3") (pinfunction "~{WP}_3") (pintype "bidirectional"))
      (node (ref "U17") (pin "22") (pinfunction "P16_22") (pintype "bidirectional"))
    )
  )
)
